# PowerSheet.net
KiCad netlist of a schematic drawn in Altium Designer
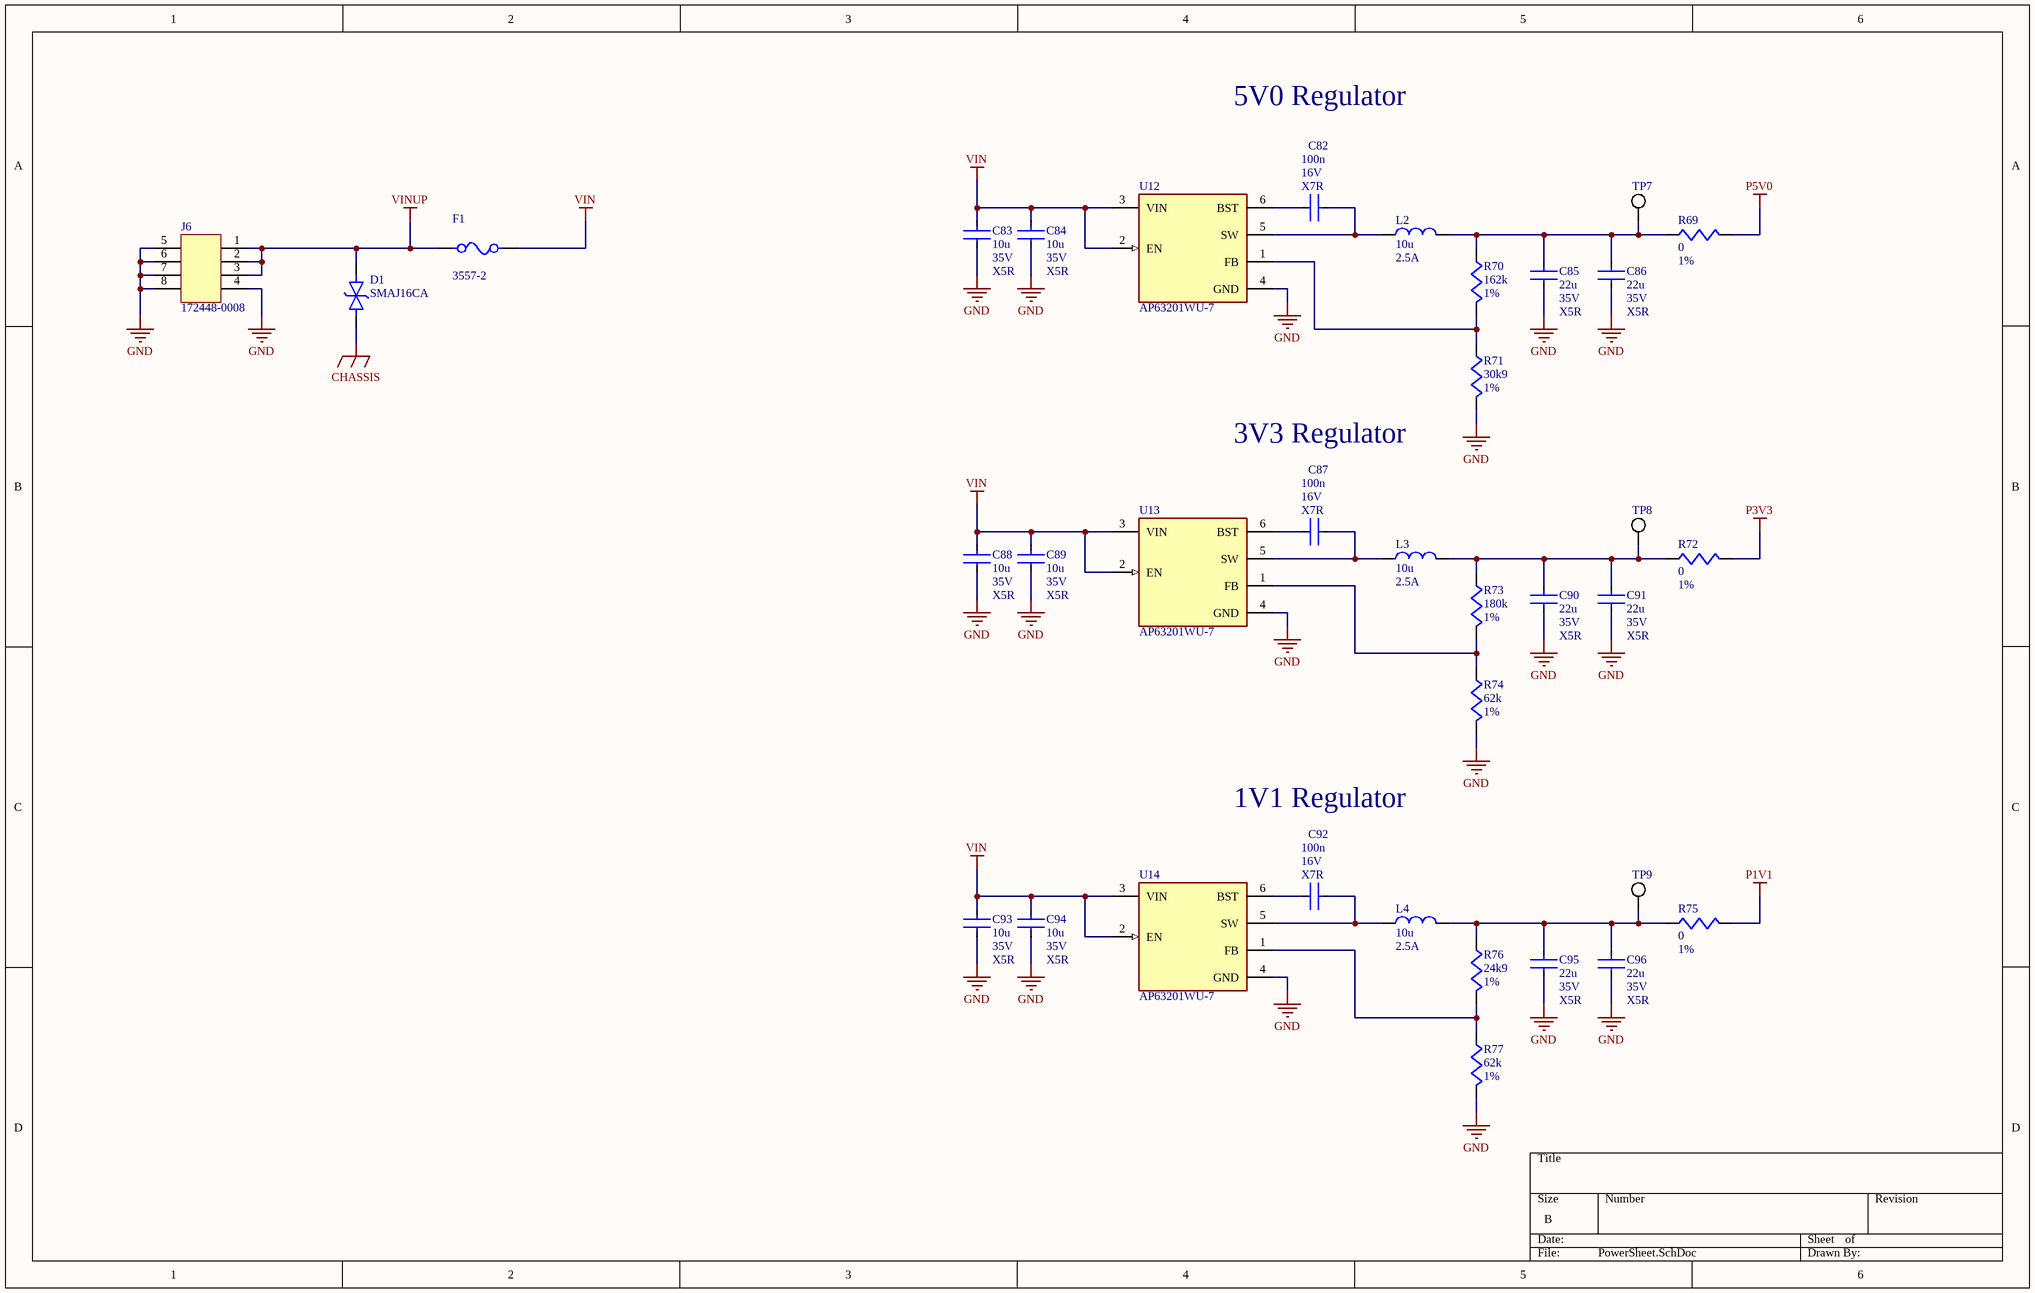
[diagram p0: PowerSheet.SchDoc]

(export (version "E")
  (design (tool "Eeschema 10.0.6"))
  (components
    (comp (ref "C82")
      (value "100n")
      (footprint "CAPC1005X06N")
      (description "16V 100nF X7R ±10% 0402 Multilayer Ceramic Capacitors MLCC - SMD/SMT ROHS")
      (fields
        (field (name "VOLTAGE") "16V")
        (field (name "DIELECTRIC") "X7R")
        (field (name "LCSC PART #") "C1525")
        (field (name "Comment") "100nF 16V 0402")
      )
      (libsource (lib "CWRU Motorsports") (part "Capacitor"))
    )
    (comp (ref "C83")
      (value "10u")
      (footprint "CAPC1608X08N")
      (description "35V 10uF X5R ±20% 0603 Multilayer Ceramic Capacitors MLCC - SMD/SMT ROHS")
      (fields
        (field (name "VOLTAGE") "35V")
        (field (name "DIELECTRIC") "X5R")
        (field (name "LCSC PART #") "C194427")
        (field (name "Comment") "10uF 35V 0603")
      )
      (libsource (lib "CWRU Motorsports") (part "Capacitor"))
    )
    (comp (ref "C84")
      (value "10u")
      (footprint "CAPC1608X08N")
      (description "35V 10uF X5R ±20% 0603 Multilayer Ceramic Capacitors MLCC - SMD/SMT ROHS")
      (fields
        (field (name "VOLTAGE") "35V")
        (field (name "DIELECTRIC") "X5R")
        (field (name "LCSC PART #") "C194427")
        (field (name "Comment") "10uF 35V 0603")
      )
      (libsource (lib "CWRU Motorsports") (part "Capacitor"))
    )
    (comp (ref "C85")
      (value "22u")
      (footprint "CAPC3225X18N")
      (description "35V 22uF X5R ±20% 1210 Multilayer Ceramic Capacitors MLCC - SMD/SMT ROHS")
      (fields
        (field (name "VOLTAGE") "35V")
        (field (name "DIELECTRIC") "X5R")
        (field (name "LCSC PART #") "C778721")
        (field (name "Comment") "22uF 35V 1210 X5R")
      )
      (libsource (lib "CWRU Motorsports") (part "Capacitor"))
    )
    (comp (ref "C86")
      (value "22u")
      (footprint "CAPC3225X18N")
      (description "35V 22uF X5R ±20% 1210 Multilayer Ceramic Capacitors MLCC - SMD/SMT ROHS")
      (fields
        (field (name "VOLTAGE") "35V")
        (field (name "DIELECTRIC") "X5R")
        (field (name "LCSC PART #") "C778721")
        (field (name "Comment") "22uF 35V 1210 X5R")
      )
      (libsource (lib "CWRU Motorsports") (part "Capacitor"))
    )
    (comp (ref "C87")
      (value "100n")
      (footprint "CAPC1005X06N")
      (description "16V 100nF X7R ±10% 0402 Multilayer Ceramic Capacitors MLCC - SMD/SMT ROHS")
      (fields
        (field (name "VOLTAGE") "16V")
        (field (name "DIELECTRIC") "X7R")
        (field (name "LCSC PART #") "C1525")
        (field (name "Comment") "100nF 16V 0402")
      )
      (libsource (lib "CWRU Motorsports") (part "Capacitor"))
    )
    (comp (ref "C88")
      (value "10u")
      (footprint "CAPC1608X08N")
      (description "35V 10uF X5R ±20% 0603 Multilayer Ceramic Capacitors MLCC - SMD/SMT ROHS")
      (fields
        (field (name "VOLTAGE") "35V")
        (field (name "DIELECTRIC") "X5R")
        (field (name "LCSC PART #") "C194427")
        (field (name "Comment") "10uF 35V 0603")
      )
      (libsource (lib "CWRU Motorsports") (part "Capacitor"))
    )
    (comp (ref "C89")
      (value "10u")
      (footprint "CAPC1608X08N")
      (description "35V 10uF X5R ±20% 0603 Multilayer Ceramic Capacitors MLCC - SMD/SMT ROHS")
      (fields
        (field (name "VOLTAGE") "35V")
        (field (name "DIELECTRIC") "X5R")
        (field (name "LCSC PART #") "C194427")
        (field (name "Comment") "10uF 35V 0603")
      )
      (libsource (lib "CWRU Motorsports") (part "Capacitor"))
    )
    (comp (ref "C90")
      (value "22u")
      (footprint "CAPC3225X18N")
      (description "35V 22uF X5R ±20% 1210 Multilayer Ceramic Capacitors MLCC - SMD/SMT ROHS")
      (fields
        (field (name "VOLTAGE") "35V")
        (field (name "DIELECTRIC") "X5R")
        (field (name "LCSC PART #") "C778721")
        (field (name "Comment") "22uF 35V 1210 X5R")
      )
      (libsource (lib "CWRU Motorsports") (part "Capacitor"))
    )
    (comp (ref "C91")
      (value "22u")
      (footprint "CAPC3225X18N")
      (description "35V 22uF X5R ±20% 1210 Multilayer Ceramic Capacitors MLCC - SMD/SMT ROHS")
      (fields
        (field (name "VOLTAGE") "35V")
        (field (name "DIELECTRIC") "X5R")
        (field (name "LCSC PART #") "C778721")
        (field (name "Comment") "22uF 35V 1210 X5R")
      )
      (libsource (lib "CWRU Motorsports") (part "Capacitor"))
    )
    (comp (ref "C92")
      (value "100n")
      (footprint "CAPC1005X06N")
      (description "16V 100nF X7R ±10% 0402 Multilayer Ceramic Capacitors MLCC - SMD/SMT ROHS")
      (fields
        (field (name "VOLTAGE") "16V")
        (field (name "DIELECTRIC") "X7R")
        (field (name "LCSC PART #") "C1525")
        (field (name "Comment") "100nF 16V 0402")
      )
      (libsource (lib "CWRU Motorsports") (part "Capacitor"))
    )
    (comp (ref "C93")
      (value "10u")
      (footprint "CAPC1608X08N")
      (description "35V 10uF X5R ±20% 0603 Multilayer Ceramic Capacitors MLCC - SMD/SMT ROHS")
      (fields
        (field (name "VOLTAGE") "35V")
        (field (name "DIELECTRIC") "X5R")
        (field (name "LCSC PART #") "C194427")
        (field (name "Comment") "10uF 35V 0603")
      )
      (libsource (lib "CWRU Motorsports") (part "Capacitor"))
    )
    (comp (ref "C94")
      (value "10u")
      (footprint "CAPC1608X08N")
      (description "35V 10uF X5R ±20% 0603 Multilayer Ceramic Capacitors MLCC - SMD/SMT ROHS")
      (fields
        (field (name "VOLTAGE") "35V")
        (field (name "DIELECTRIC") "X5R")
        (field (name "LCSC PART #") "C194427")
        (field (name "Comment") "10uF 35V 0603")
      )
      (libsource (lib "CWRU Motorsports") (part "Capacitor"))
    )
    (comp (ref "C95")
      (value "22u")
      (footprint "CAPC3225X18N")
      (description "35V 22uF X5R ±20% 1210 Multilayer Ceramic Capacitors MLCC - SMD/SMT ROHS")
      (fields
        (field (name "VOLTAGE") "35V")
        (field (name "DIELECTRIC") "X5R")
        (field (name "LCSC PART #") "C778721")
        (field (name "Comment") "22uF 35V 1210 X5R")
      )
      (libsource (lib "CWRU Motorsports") (part "Capacitor"))
    )
    (comp (ref "C96")
      (value "22u")
      (footprint "CAPC3225X18N")
      (description "35V 22uF X5R ±20% 1210 Multilayer Ceramic Capacitors MLCC - SMD/SMT ROHS")
      (fields
        (field (name "VOLTAGE") "35V")
        (field (name "DIELECTRIC") "X5R")
        (field (name "LCSC PART #") "C778721")
        (field (name "Comment") "22uF 35V 1210 X5R")
      )
      (libsource (lib "CWRU Motorsports") (part "Capacitor"))
    )
    (comp (ref "D1")
      (value "SMAJ16CA")
      (footprint "DO-214AC")
      (description "26V 17.8V Bidirectional 16V SMA(DO-214AC) ESD and Surge Protection (TVS/ESD) ROHS")
      (libsource (lib "CWRU Motorsports") (part "DIODE_TVS"))
    )
    (comp (ref "F1")
      (value "3557-2")
      (footprint "3557-2-Footprint-1")
      (description "Fuse Block 30 A 500V 1 Circuit Blade Through Hole")
      (fields (field (name "LCSC PART #") "C19727304"))
      (libsource (lib "CWRU Motorsports") (part "Fuse"))
    )
    (comp (ref "J6")
      (value "172448-0008")
      (footprint "FP-172448-0008-MFG")
      (description "Rectangular Power Connector, 8 Contact(s), Male, Solder Terminal")
      (libsource (lib "CWRU Motorsports") (part "172448-0008"))
    )
    (comp (ref "L2")
      (value "10u")
      (footprint "10uH 2.5A SL0420-100M-Footprint-1")
      (description "2A 10uH ±20% 2.5A SMD,4.5x4.1mm Inductors (SMD) ROHS")
      (fields (field (name "SATURATION CURRENT") "2.5A") (field (name "Comment") "10uH 2.5A SL0420-100M"))
      (libsource (lib "CWRU Motorsports") (part "Inductor"))
    )
    (comp (ref "L3")
      (value "10u")
      (footprint "10uH 2.5A SL0420-100M-Footprint-1")
      (description "2A 10uH ±20% 2.5A SMD,4.5x4.1mm Inductors (SMD) ROHS")
      (fields (field (name "SATURATION CURRENT") "2.5A") (field (name "Comment") "10uH 2.5A SL0420-100M"))
      (libsource (lib "CWRU Motorsports") (part "Inductor"))
    )
    (comp (ref "L4")
      (value "10u")
      (footprint "10uH 2.5A SL0420-100M-Footprint-1")
      (description "2A 10uH ±20% 2.5A SMD,4.5x4.1mm Inductors (SMD) ROHS")
      (fields (field (name "SATURATION CURRENT") "2.5A") (field (name "Comment") "10uH 2.5A SL0420-100M"))
      (libsource (lib "CWRU Motorsports") (part "Inductor"))
    )
    (comp (ref "R69")
      (value "0")
      (footprint "RESC2013X06M")
      (description "125mW Thick Film Resistors 150V ±5% 0Ω 0805 Chip Resistor - Surface Mount ROHS")
      (fields
        (field (name "TOLERANCE") "1%")
        (field (name "LCSC PART #") "C96345")
        (field (name "Comment") "0 Ohm 1% 0805")
      )
      (libsource (lib "CWRU Motorsports") (part "Resistor"))
    )
    (comp (ref "R70")
      (value "162k")
      (footprint "RESC1005X04M")
      (description "62.5mW Thick Film Resistors 50V ±100ppm/℃ ±1% 162kΩ 0402 Chip Resistor - Surface Mount ROHS")
      (fields
        (field (name "TOLERANCE") "1%")
        (field (name "LCSC PART #") "C54068")
        (field (name "Comment") "162k 1% 0402")
      )
      (libsource (lib "CWRU Motorsports") (part "Resistor"))
    )
    (comp (ref "R71")
      (value "30k9")
      (footprint "RESC1005X04M")
      (description "62.5mW Thick Film Resistors 50V ±100ppm/℃ ±1% 30.9kΩ 0402 Chip Resistor - Surface Mount ROHS")
      (fields
        (field (name "TOLERANCE") "1%")
        (field (name "LCSC PART #") "C185428")
        (field (name "Comment") "30.9k 1% 0402")
      )
      (libsource (lib "CWRU Motorsports") (part "Resistor"))
    )
    (comp (ref "R72")
      (value "0")
      (footprint "RESC2013X06M")
      (description "125mW Thick Film Resistors 150V ±5% 0Ω 0805 Chip Resistor - Surface Mount ROHS")
      (fields
        (field (name "TOLERANCE") "1%")
        (field (name "LCSC PART #") "C96345")
        (field (name "Comment") "0 Ohm 1% 0805")
      )
      (libsource (lib "CWRU Motorsports") (part "Resistor"))
    )
    (comp (ref "R73")
      (value "180k")
      (footprint "RESC1005X04M")
      (description "62.5mW Thick Film Resistors 50V ±100ppm/℃ ±1% 180kΩ 0402 Chip Resistor - Surface Mount ROHS")
      (fields
        (field (name "TOLERANCE") "1%")
        (field (name "LCSC PART #") "C144794")
        (field (name "Comment") "180k 1% 0402")
      )
      (libsource (lib "CWRU Motorsports") (part "Resistor"))
    )
    (comp (ref "R74")
      (value "62k")
      (footprint "RESC1005X04M")
      (description "62.5mW Thick Film Resistors 50V ±100ppm/℃ ±1% 62kΩ 0402 Chip Resistor - Surface Mount ROHS")
      (fields
        (field (name "TOLERANCE") "1%")
        (field (name "LCSC PART #") "C137950")
        (field (name "Comment") "62k 1% 0402")
      )
      (libsource (lib "CWRU Motorsports") (part "Resistor"))
    )
    (comp (ref "R75")
      (value "0")
      (footprint "RESC2013X06M")
      (description "125mW Thick Film Resistors 150V ±5% 0Ω 0805 Chip Resistor - Surface Mount ROHS")
      (fields
        (field (name "TOLERANCE") "1%")
        (field (name "LCSC PART #") "C96345")
        (field (name "Comment") "0 Ohm 1% 0805")
      )
      (libsource (lib "CWRU Motorsports") (part "Resistor"))
    )
    (comp (ref "R76")
      (value "24k9")
      (footprint "RESC1005X04M")
      (description "62.5mW Thick Film Resistors 50V ±100ppm/℃ ±1% 24.9kΩ 0402 Chip Resistor - Surface Mount ROHS")
      (fields
        (field (name "TOLERANCE") "1%")
        (field (name "LCSC PART #") "C25874")
        (field (name "Comment") "24.9k 1% 0402")
      )
      (libsource (lib "CWRU Motorsports") (part "Resistor"))
    )
    (comp (ref "R77")
      (value "62k")
      (footprint "RESC1005X04M")
      (description "62.5mW Thick Film Resistors 50V ±100ppm/℃ ±1% 62kΩ 0402 Chip Resistor - Surface Mount ROHS")
      (fields
        (field (name "TOLERANCE") "1%")
        (field (name "LCSC PART #") "C137950")
        (field (name "Comment") "62k 1% 0402")
      )
      (libsource (lib "CWRU Motorsports") (part "Resistor"))
    )
    (comp (ref "TP7")
      (value "SMT Test Point 5015")
      (footprint "New footprint 1")
      (description "PC Test Point, Miniature Phosphor Bronze Silver Plating Surface Mount Mounting Type")
      (fields (field (name "LCSC PART #") "C5199798"))
      (libsource (lib "CWRU Motorsports") (part "Test Point"))
    )
    (comp (ref "TP8")
      (value "SMT Test Point 5015")
      (footprint "New footprint 1")
      (description "PC Test Point, Miniature Phosphor Bronze Silver Plating Surface Mount Mounting Type")
      (fields (field (name "LCSC PART #") "C5199798"))
      (libsource (lib "CWRU Motorsports") (part "Test Point"))
    )
    (comp (ref "TP9")
      (value "SMT Test Point 5015")
      (footprint "New footprint 1")
      (description "PC Test Point, Miniature Phosphor Bronze Silver Plating Surface Mount Mounting Type")
      (fields (field (name "LCSC PART #") "C5199798"))
      (libsource (lib "CWRU Motorsports") (part "Test Point"))
    )
    (comp (ref "U12")
      (value "AP63201WU-7")
      (footprint "FP-TSOT26-IPC_B")
      (description "Switching Regulator")
      (fields (field (name "LCSC PART #") "C2071044"))
      (libsource (lib "CWRU Motorsports") (part "852620ac253781219691b45ee1e20b7"))
    )
    (comp (ref "U13")
      (value "AP63201WU-7")
      (footprint "FP-TSOT26-IPC_B")
      (description "Switching Regulator")
      (fields (field (name "LCSC PART #") "C2071044"))
      (libsource (lib "CWRU Motorsports") (part "852620ac253781219691b45ee1e20b7"))
    )
    (comp (ref "U14")
      (value "AP63201WU-7")
      (footprint "FP-TSOT26-IPC_B")
      (description "Switching Regulator")
      (fields (field (name "LCSC PART #") "C2071044"))
      (libsource (lib "CWRU Motorsports") (part "852620ac253781219691b45ee1e20b7"))
    )
  )
  (nets
    (net (code "1") (name "CHASSIS") (class "Default")
      (node (ref "D1") (pin "2") (pinfunction "2_2") (pintype "passive"))
    )
    (net (code "2") (name "GND") (class "Default")
      (node (ref "C83") (pin "2") (pinfunction "2_2") (pintype "passive"))
      (node (ref "C84") (pin "2") (pinfunction "2_2") (pintype "passive"))
      (node (ref "C85") (pin "2") (pinfunction "2_2") (pintype "passive"))
      (node (ref "C86") (pin "2") (pinfunction "2_2") (pintype "passive"))
      (node (ref "C88") (pin "2") (pinfunction "2_2") (pintype "passive"))
      (node (ref "C89") (pin "2") (pinfunction "2_2") (pintype "passive"))
      (node (ref "C90") (pin "2") (pinfunction "2_2") (pintype "passive"))
      (node (ref "C91") (pin "2") (pinfunction "2_2") (pintype "passive"))
      (node (ref "C93") (pin "2") (pinfunction "2_2") (pintype "passive"))
      (node (ref "C94") (pin "2") (pinfunction "2_2") (pintype "passive"))
      (node (ref "C95") (pin "2") (pinfunction "2_2") (pintype "passive"))
      (node (ref "C96") (pin "2") (pinfunction "2_2") (pintype "passive"))
      (node (ref "J6") (pin "4") (pintype "passive"))
      (node (ref "J6") (pin "5") (pintype "passive"))
      (node (ref "J6") (pin "6") (pintype "passive"))
      (node (ref "J6") (pin "7") (pintype "passive"))
      (node (ref "J6") (pin "8") (pintype "passive"))
      (node (ref "R71") (pin "2") (pinfunction "2_2") (pintype "passive"))
      (node (ref "R74") (pin "2") (pinfunction "2_2") (pintype "passive"))
      (node (ref "R77") (pin "2") (pinfunction "2_2") (pintype "passive"))
      (node (ref "U12") (pin "4") (pinfunction "GND_4") (pintype "power_in"))
      (node (ref "U13") (pin "4") (pinfunction "GND_4") (pintype "power_in"))
      (node (ref "U14") (pin "4") (pinfunction "GND_4") (pintype "power_in"))
    )
    (net (code "3") (name "Net-(C85-Pad1)") (class "Default")
      (node (ref "C85") (pin "1") (pinfunction "1_1") (pintype "passive"))
      (node (ref "C86") (pin "1") (pinfunction "1_1") (pintype "passive"))
      (node (ref "L2") (pin "2") (pinfunction "2_2") (pintype "passive"))
      (node (ref "R69") (pin "1") (pinfunction "1_1") (pintype "passive"))
      (node (ref "R70") (pin "1") (pinfunction "1_1") (pintype "passive"))
      (node (ref "TP7") (pin "0") (pinfunction "0_0") (pintype "passive"))
    )
    (net (code "4") (name "Net-(C90-Pad1)") (class "Default")
      (node (ref "C90") (pin "1") (pinfunction "1_1") (pintype "passive"))
      (node (ref "C91") (pin "1") (pinfunction "1_1") (pintype "passive"))
      (node (ref "L3") (pin "2") (pinfunction "2_2") (pintype "passive"))
      (node (ref "R72") (pin "1") (pinfunction "1_1") (pintype "passive"))
      (node (ref "R73") (pin "1") (pinfunction "1_1") (pintype "passive"))
      (node (ref "TP8") (pin "0") (pinfunction "0_0") (pintype "passive"))
    )
    (net (code "5") (name "Net-(C95-Pad1)") (class "Default")
      (node (ref "C95") (pin "1") (pinfunction "1_1") (pintype "passive"))
      (node (ref "C96") (pin "1") (pinfunction "1_1") (pintype "passive"))
      (node (ref "L4") (pin "2") (pinfunction "2_2") (pintype "passive"))
      (node (ref "R75") (pin "1") (pinfunction "1_1") (pintype "passive"))
      (node (ref "R76") (pin "1") (pinfunction "1_1") (pintype "passive"))
      (node (ref "TP9") (pin "0") (pinfunction "0_0") (pintype "passive"))
    )
    (net (code "6") (name "Net-(U12-BST)") (class "Default")
      (node (ref "C82") (pin "2") (pinfunction "2_2") (pintype "passive"))
      (node (ref "U12") (pin "6") (pinfunction "BST_6") (pintype "passive"))
    )
    (net (code "7") (name "Net-(U12-FB)") (class "Default")
      (node (ref "R70") (pin "2") (pinfunction "2_2") (pintype "passive"))
      (node (ref "R71") (pin "1") (pinfunction "1_1") (pintype "passive"))
      (node (ref "U12") (pin "1") (pinfunction "FB_1") (pintype "passive"))
    )
    (net (code "8") (name "Net-(U12-SW)") (class "Default")
      (node (ref "C82") (pin "1") (pinfunction "1_1") (pintype "passive"))
      (node (ref "L2") (pin "1") (pinfunction "1_1") (pintype "passive"))
      (node (ref "U12") (pin "5") (pinfunction "SW_5") (pintype "passive"))
    )
    (net (code "9") (name "Net-(U13-BST)") (class "Default")
      (node (ref "C87") (pin "2") (pinfunction "2_2") (pintype "passive"))
      (node (ref "U13") (pin "6") (pinfunction "BST_6") (pintype "passive"))
    )
    (net (code "10") (name "Net-(U13-FB)") (class "Default")
      (node (ref "R73") (pin "2") (pinfunction "2_2") (pintype "passive"))
      (node (ref "R74") (pin "1") (pinfunction "1_1") (pintype "passive"))
      (node (ref "U13") (pin "1") (pinfunction "FB_1") (pintype "passive"))
    )
    (net (code "11") (name "Net-(U13-SW)") (class "Default")
      (node (ref "C87") (pin "1") (pinfunction "1_1") (pintype "passive"))
      (node (ref "L3") (pin "1") (pinfunction "1_1") (pintype "passive"))
      (node (ref "U13") (pin "5") (pinfunction "SW_5") (pintype "passive"))
    )
    (net (code "12") (name "Net-(U14-BST)") (class "Default")
      (node (ref "C92") (pin "2") (pinfunction "2_2") (pintype "passive"))
      (node (ref "U14") (pin "6") (pinfunction "BST_6") (pintype "passive"))
    )
    (net (code "13") (name "Net-(U14-FB)") (class "Default")
      (node (ref "R76") (pin "2") (pinfunction "2_2") (pintype "passive"))
      (node (ref "R77") (pin "1") (pinfunction "1_1") (pintype "passive"))
      (node (ref "U14") (pin "1") (pinfunction "FB_1") (pintype "passive"))
    )
    (net (code "14") (name "Net-(U14-SW)") (class "Default")
      (node (ref "C92") (pin "1") (pinfunction "1_1") (pintype "passive"))
      (node (ref "L4") (pin "1") (pinfunction "1_1") (pintype "passive"))
      (node (ref "U14") (pin "5") (pinfunction "SW_5") (pintype "passive"))
    )
    (net (code "15") (name "P1V1") (class "Default")
      (node (ref "R75") (pin "2") (pinfunction "2_2") (pintype "passive"))
    )
    (net (code "16") (name "P3V3") (class "Default")
      (node (ref "R72") (pin "2") (pinfunction "2_2") (pintype "passive"))
    )
    (net (code "17") (name "P5V0") (class "Default")
      (node (ref "R69") (pin "2") (pinfunction "2_2") (pintype "passive"))
    )
    (net (code "18") (name "VIN") (class "Default")
      (node (ref "C83") (pin "1") (pinfunction "1_1") (pintype "passive"))
      (node (ref "C84") (pin "1") (pinfunction "1_1") (pintype "passive"))
      (node (ref "C88") (pin "1") (pinfunction "1_1") (pintype "passive"))
      (node (ref "C89") (pin "1") (pinfunction "1_1") (pintype "passive"))
      (node (ref "C93") (pin "1") (pinfunction "1_1") (pintype "passive"))
      (node (ref "C94") (pin "1") (pinfunction "1_1") (pintype "passive"))
      (node (ref "F1") (pin "2") (pinfunction "2_2") (pintype "passive"))
      (node (ref "U12") (pin "2") (pinfunction "EN_2") (pintype "input"))
      (node (ref "U12") (pin "3") (pinfunction "VIN_3") (pintype "power_in"))
      (node (ref "U13") (pin "2") (pinfunction "EN_2") (pintype "input"))
      (node (ref "U13") (pin "3") (pinfunction "VIN_3") (pintype "power_in"))
      (node (ref "U14") (pin "2") (pinfunction "EN_2") (pintype "input"))
      (node (ref "U14") (pin "3") (pinfunction "VIN_3") (pintype "power_in"))
    )
    (net (code "19") (name "VINUP") (class "Default")
      (node (ref "D1") (pin "1") (pinfunction "1_1") (pintype "passive"))
      (node (ref "F1") (pin "1") (pinfunction "1_1") (pintype "passive"))
      (node (ref "J6") (pin "1") (pintype "passive"))
      (node (ref "J6") (pin "2") (pintype "passive"))
      (node (ref "J6") (pin "3") (pintype "passive"))
    )
  )
)
